# L298N.net
KiCad netlist of a schematic drawn in Altium Designer
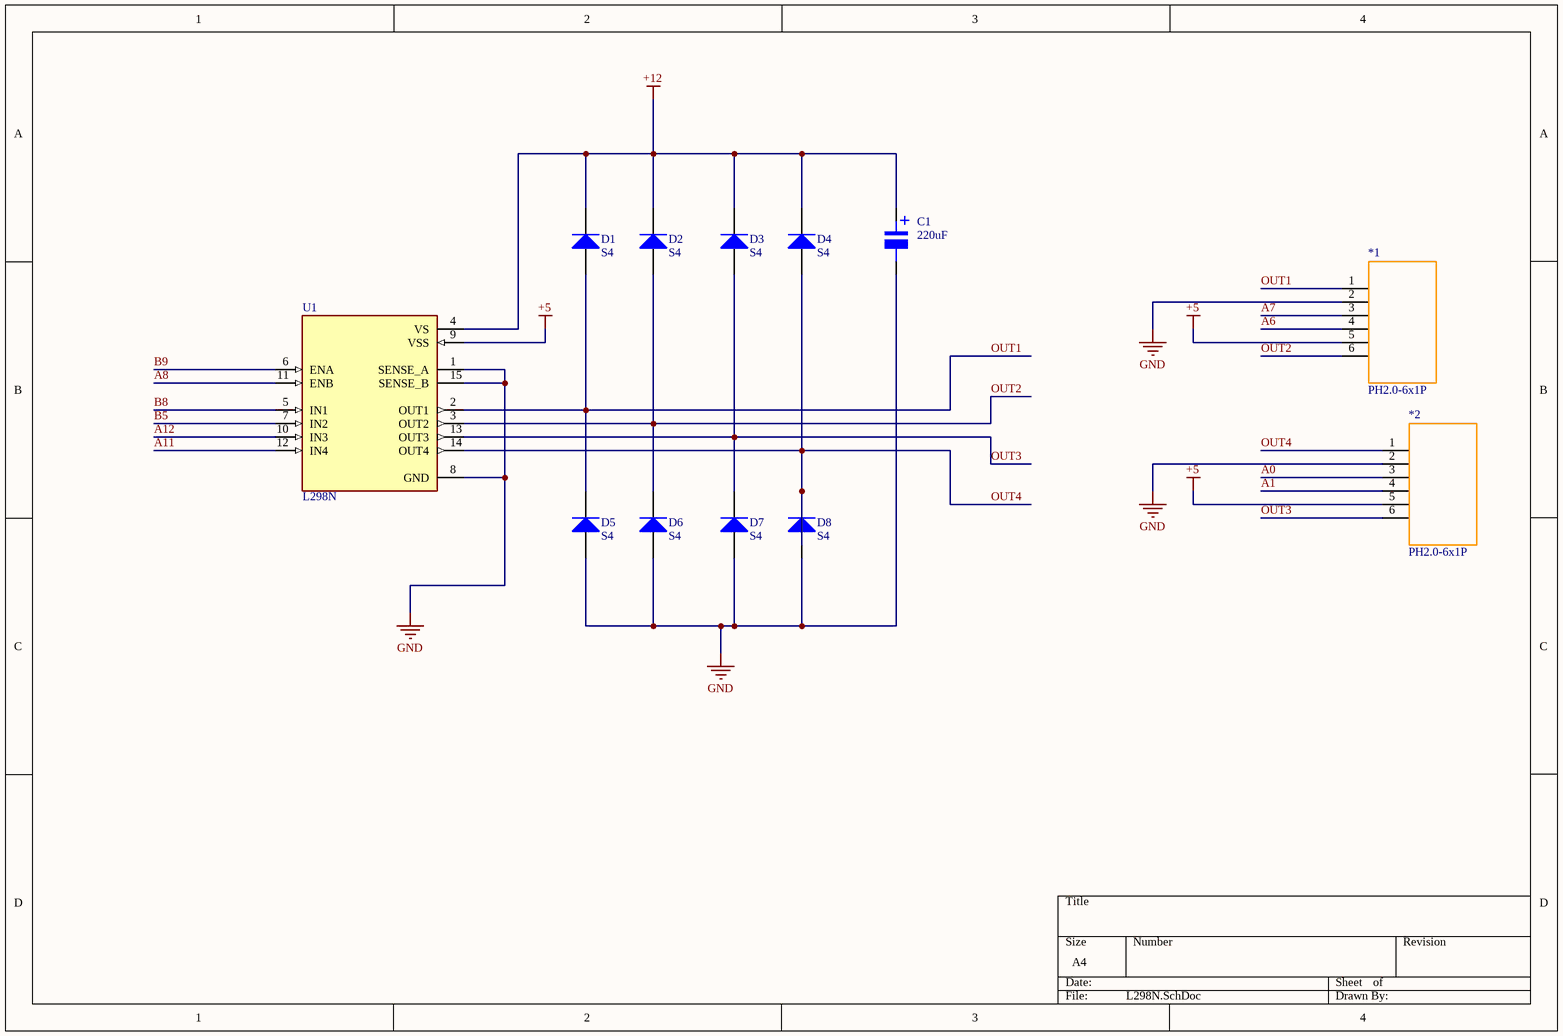
[diagram p0: L298N.SchDoc]

(export (version "E")
  (design (tool "Eeschema 10.0.6"))
  (components
    (comp (ref "*1")
      (value "PH2.0-6x1P")
      (footprint "PH2.0-6P")
      (libsource (lib "my_lib") (part "PH2.0-6x1P"))
    )
    (comp (ref "*2")
      (value "PH2.0-6x1P")
      (footprint "PH2.0-6P")
      (libsource (lib "my_lib") (part "PH2.0-6x1P"))
    )
    (comp (ref "C1")
      (value "220uF")
      (footprint "tu nhom 8 (f)")
      (description "Dán")
      (libsource (lib "Altium_Lib_by_KhueNguyenCreator") (part "Tu Nhom 220uF 25V"))
    )
    (comp (ref "D1")
      (value "S4")
      (footprint "DIODE SOD-123")
      (description "Dán")
      (libsource (lib "Altium_Lib_by_KhueNguyenCreator") (part "Diode S4"))
    )
    (comp (ref "D2")
      (value "S4")
      (footprint "DIODE SOD-123")
      (description "Dán")
      (libsource (lib "Altium_Lib_by_KhueNguyenCreator") (part "Diode S4"))
    )
    (comp (ref "D3")
      (value "S4")
      (footprint "DIODE SOD-123")
      (description "Dán")
      (libsource (lib "Altium_Lib_by_KhueNguyenCreator") (part "Diode S4"))
    )
    (comp (ref "D4")
      (value "S4")
      (footprint "DIODE SOD-123")
      (description "Dán")
      (libsource (lib "Altium_Lib_by_KhueNguyenCreator") (part "Diode S4"))
    )
    (comp (ref "D5")
      (value "S4")
      (footprint "DIODE SOD-123")
      (description "Dán")
      (libsource (lib "Altium_Lib_by_KhueNguyenCreator") (part "Diode S4"))
    )
    (comp (ref "D6")
      (value "S4")
      (footprint "DIODE SOD-123")
      (description "Dán")
      (libsource (lib "Altium_Lib_by_KhueNguyenCreator") (part "Diode S4"))
    )
    (comp (ref "D7")
      (value "S4")
      (footprint "DIODE SOD-123")
      (description "Dán")
      (libsource (lib "Altium_Lib_by_KhueNguyenCreator") (part "Diode S4"))
    )
    (comp (ref "D8")
      (value "S4")
      (footprint "DIODE SOD-123")
      (description "Dán")
      (libsource (lib "Altium_Lib_by_KhueNguyenCreator") (part "Diode S4"))
    )
    (comp (ref "U1")
      (value "L298N")
      (footprint "L298N")
      (description "Half Bridge _4_ Driver DC Motors, Relays, Solenoids, Stepper Motors Bipolar 15-Multiwatt")
      (fields (field (name "MF") "STMicroelectronics"))
      (libsource (lib "Altium_Lib_by_KhueNguyenCreator") (part "L298N"))
    )
  )
  (nets
    (net (code "1") (name "+5") (class "Default")
      (node (ref "*1") (pin "5") (pinfunction "5_5") (pintype "passive"))
      (node (ref "*2") (pin "5") (pinfunction "5_5") (pintype "passive"))
      (node (ref "U1") (pin "9") (pinfunction "VSS_9") (pintype "input"))
    )
    (net (code "2") (name "+12") (class "Default")
      (node (ref "C1") (pin "1") (pinfunction "1_1") (pintype "passive"))
      (node (ref "D1") (pin "2") (pinfunction "K_2") (pintype "passive"))
      (node (ref "D2") (pin "2") (pinfunction "K_2") (pintype "passive"))
      (node (ref "D3") (pin "2") (pinfunction "K_2") (pintype "passive"))
      (node (ref "D4") (pin "2") (pinfunction "K_2") (pintype "passive"))
      (node (ref "U1") (pin "4") (pinfunction "VS_4") (pintype "power_in"))
    )
    (net (code "3") (name "/A0") (class "Default")
      (node (ref "*2") (pin "3") (pinfunction "3_3") (pintype "passive"))
    )
    (net (code "4") (name "/A1") (class "Default")
      (node (ref "*2") (pin "4") (pinfunction "4_4") (pintype "passive"))
    )
    (net (code "5") (name "/A6") (class "Default")
      (node (ref "*1") (pin "4") (pinfunction "4_4") (pintype "passive"))
    )
    (net (code "6") (name "/A7") (class "Default")
      (node (ref "*1") (pin "3") (pinfunction "3_3") (pintype "passive"))
    )
    (net (code "7") (name "/A8") (class "Default")
      (node (ref "U1") (pin "11") (pinfunction "ENB_11") (pintype "input"))
    )
    (net (code "8") (name "/A11") (class "Default")
      (node (ref "U1") (pin "12") (pinfunction "IN4_12") (pintype "input"))
    )
    (net (code "9") (name "/A12") (class "Default")
      (node (ref "U1") (pin "10") (pinfunction "IN3_10") (pintype "input"))
    )
    (net (code "10") (name "/B5") (class "Default")
      (node (ref "U1") (pin "7") (pinfunction "IN2_7") (pintype "input"))
    )
    (net (code "11") (name "/B8") (class "Default")
      (node (ref "U1") (pin "5") (pinfunction "IN1_5") (pintype "input"))
    )
    (net (code "12") (name "/B9") (class "Default")
      (node (ref "U1") (pin "6") (pinfunction "ENA_6") (pintype "input"))
    )
    (net (code "13") (name "/OUT1") (class "Default")
      (node (ref "*1") (pin "1") (pinfunction "1_1") (pintype "passive"))
      (node (ref "D1") (pin "1") (pinfunction "A_1") (pintype "passive"))
      (node (ref "D5") (pin "2") (pinfunction "K_2") (pintype "passive"))
      (node (ref "U1") (pin "2") (pinfunction "OUT1_2") (pintype "output"))
    )
    (net (code "14") (name "/OUT2") (class "Default")
      (node (ref "*1") (pin "6") (pinfunction "6_6") (pintype "passive"))
      (node (ref "D2") (pin "1") (pinfunction "A_1") (pintype "passive"))
      (node (ref "D6") (pin "2") (pinfunction "K_2") (pintype "passive"))
      (node (ref "U1") (pin "3") (pinfunction "OUT2_3") (pintype "output"))
    )
    (net (code "15") (name "/OUT3") (class "Default")
      (node (ref "*2") (pin "6") (pinfunction "6_6") (pintype "passive"))
      (node (ref "D3") (pin "1") (pinfunction "A_1") (pintype "passive"))
      (node (ref "D7") (pin "2") (pinfunction "K_2") (pintype "passive"))
      (node (ref "U1") (pin "13") (pinfunction "OUT3_13") (pintype "output"))
    )
    (net (code "16") (name "/OUT4") (class "Default")
      (node (ref "*2") (pin "1") (pinfunction "1_1") (pintype "passive"))
      (node (ref "D4") (pin "1") (pinfunction "A_1") (pintype "passive"))
      (node (ref "D8") (pin "2") (pinfunction "K_2") (pintype "passive"))
      (node (ref "U1") (pin "14") (pinfunction "OUT4_14") (pintype "output"))
    )
    (net (code "17") (name "GND") (class "Default")
      (node (ref "*1") (pin "2") (pinfunction "0_2") (pintype "passive"))
      (node (ref "*2") (pin "2") (pinfunction "0_2") (pintype "passive"))
      (node (ref "C1") (pin "2") (pinfunction "2_2") (pintype "passive"))
      (node (ref "D5") (pin "1") (pinfunction "A_1") (pintype "passive"))
      (node (ref "D6") (pin "1") (pinfunction "A_1") (pintype "passive"))
      (node (ref "D7") (pin "1") (pinfunction "A_1") (pintype "passive"))
      (node (ref "D8") (pin "1") (pinfunction "A_1") (pintype "passive"))
      (node (ref "U1") (pin "1") (pinfunction "SENSE_A_1") (pintype "passive"))
      (node (ref "U1") (pin "15") (pinfunction "SENSE_B_15") (pintype "passive"))
      (node (ref "U1") (pin "8") (pinfunction "GND_8") (pintype "power_in"))
    )
  )
)
